# PAGE2.net
KiCad netlist of a schematic drawn in Altium Designer
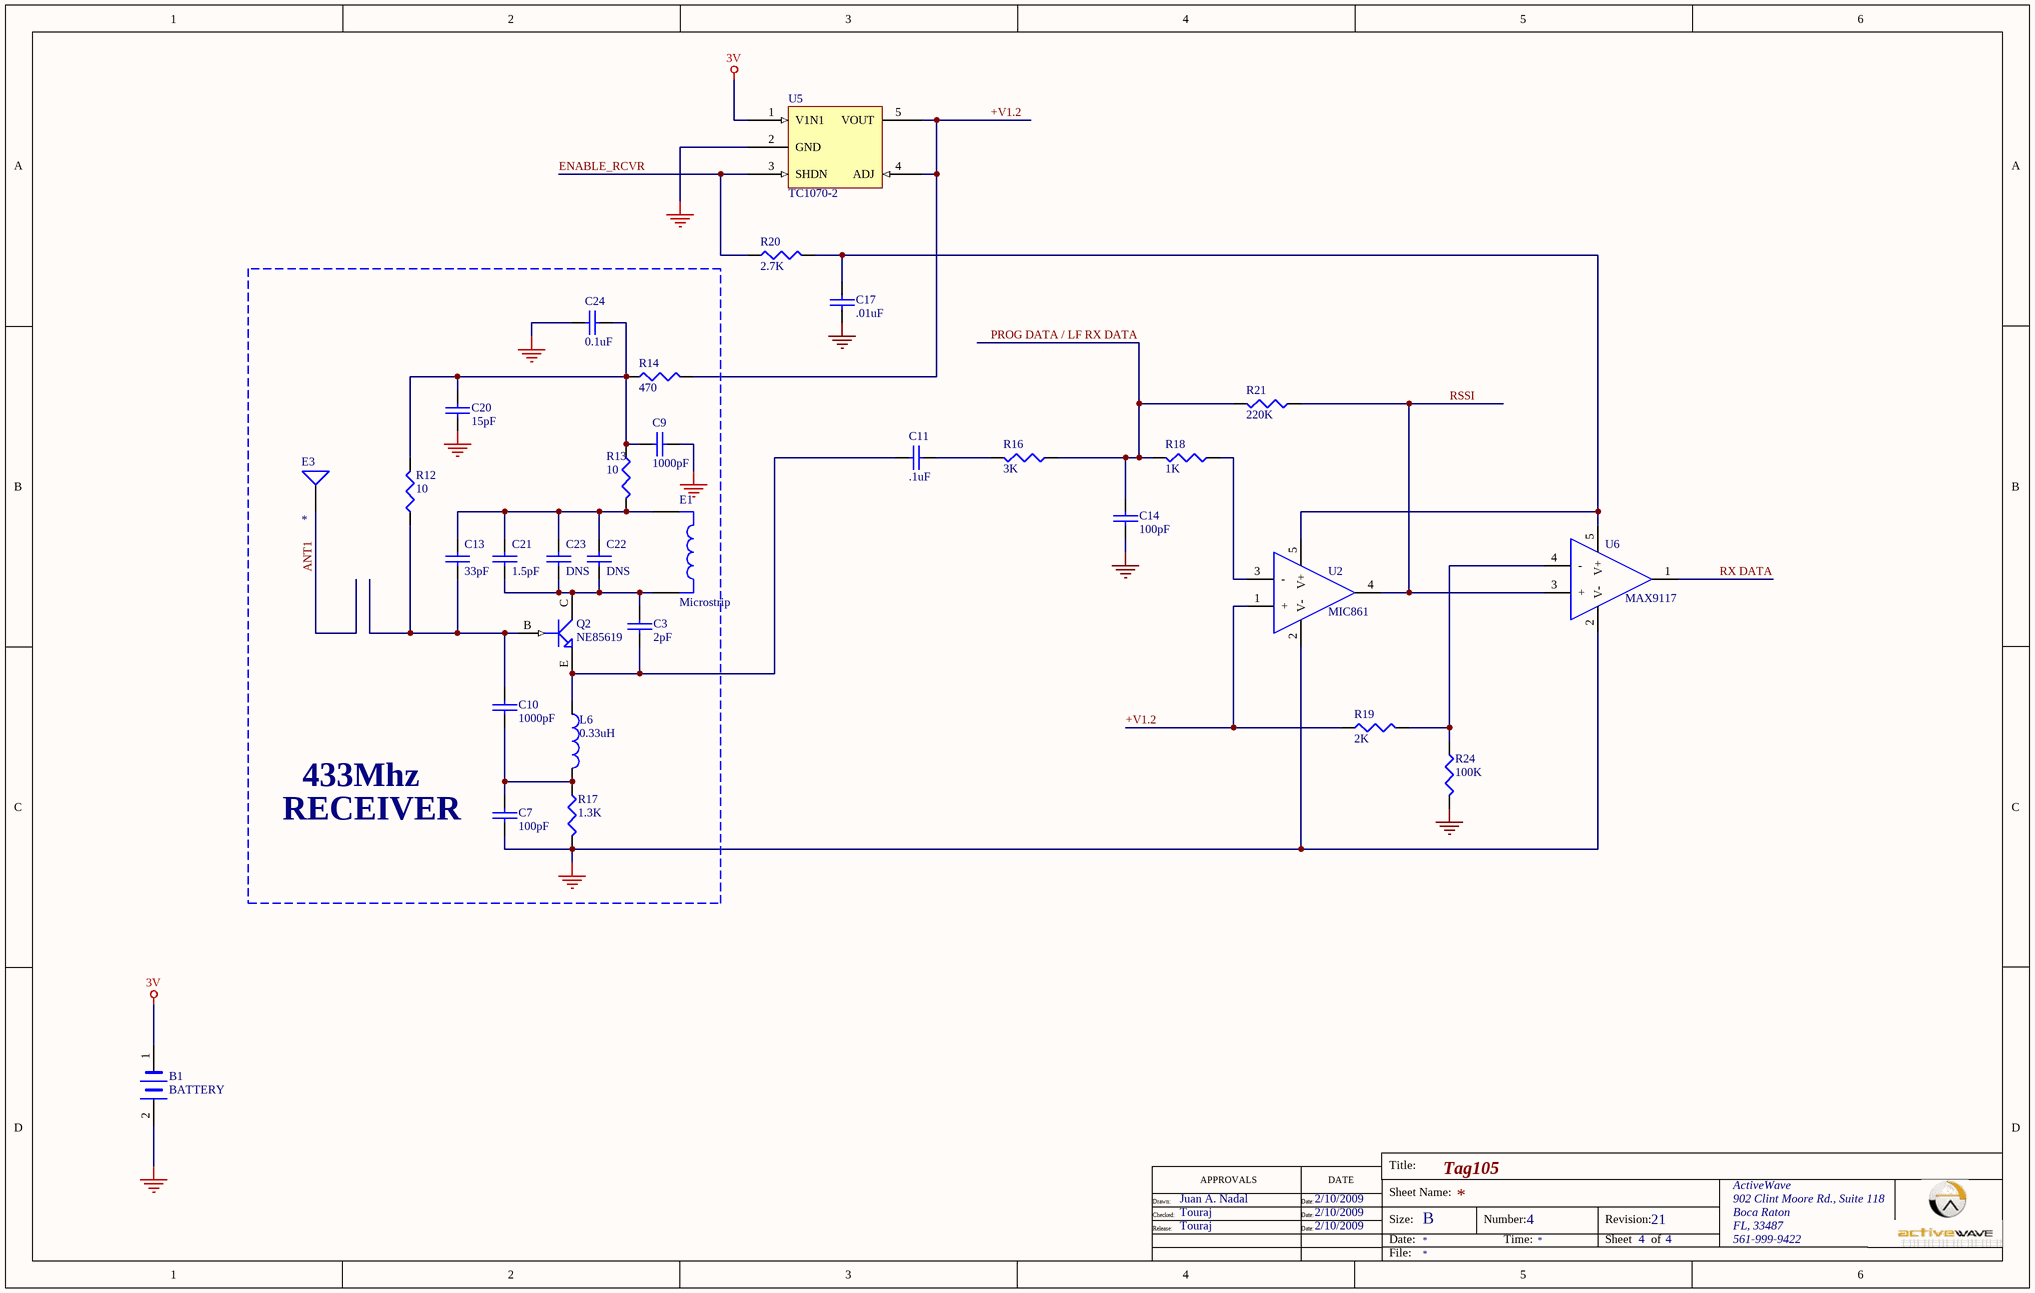
[diagram p0: PAGE2.schdoc]

(export (version "E")
  (design (tool "Eeschema 10.0.6"))
  (components
    (comp (ref "B1")
      (value "BATTERY")
      (footprint "BATTERY COIN CR2032")
      (description "Battery")
      (libsource (lib "*") (part "BATTERY"))
    )
    (comp (ref "C3")
      (value "2pF")
      (footprint "0603")
      (description "Capacitor")
      (libsource (lib "ActiveWave MasterLib") (part "CAP-0603"))
    )
    (comp (ref "C7")
      (value "100pF")
      (footprint "0603")
      (description "Capacitor")
      (libsource (lib "ActiveWave MasterLib") (part "CAP-0603"))
    )
    (comp (ref "C9")
      (value "1000pF")
      (footprint "0603")
      (description "Capacitor")
      (libsource (lib "ActiveWave MasterLib") (part "CAP-0603"))
    )
    (comp (ref "C10")
      (value "1000pF")
      (footprint "0603")
      (description "Capacitor")
      (libsource (lib "ActiveWave MasterLib") (part "CAP-0603"))
    )
    (comp (ref "C11")
      (value ".1uF")
      (footprint "0603")
      (description "Capacitor")
      (libsource (lib "ActiveWave MasterLib") (part "CAP-0603"))
    )
    (comp (ref "C13")
      (value "33pF")
      (footprint "0603")
      (description "Capacitor")
      (libsource (lib "ActiveWave MasterLib") (part "CAP-0603"))
    )
    (comp (ref "C14")
      (value "100pF")
      (footprint "0603")
      (description "Capacitor")
      (libsource (lib "ActiveWave MasterLib") (part "CAP-0603"))
    )
    (comp (ref "C17")
      (value ".01uF")
      (footprint "0603")
      (description "Capacitor")
      (libsource (lib "ActiveWave MasterLib") (part "CAP-0603"))
    )
    (comp (ref "C20")
      (value "15pF")
      (footprint "0603")
      (description "Capacitor")
      (libsource (lib "ActiveWave MasterLib") (part "CAP-0603"))
    )
    (comp (ref "C21")
      (value "1.5pF")
      (footprint "0603")
      (description "Capacitor")
      (libsource (lib "ActiveWave MasterLib") (part "CAP-0603"))
    )
    (comp (ref "C22")
      (value "DNS")
      (footprint "0603")
      (description "Capacitor")
      (libsource (lib "ActiveWave MasterLib") (part "CAP-0603"))
    )
    (comp (ref "C23")
      (value "DNS")
      (footprint "0603")
      (description "Capacitor")
      (libsource (lib "ActiveWave MasterLib") (part "CAP-0603"))
    )
    (comp (ref "C24")
      (value "0.1uF")
      (footprint "0603")
      (description "Capacitor")
      (libsource (lib "ActiveWave MasterLib") (part "CAP-0603"))
    )
    (comp (ref "E1")
      (value "Microstrip")
      (footprint "Antenna")
      (fields (field (name "ITEM-DESCRIPTION") "Microstrip"))
      (libsource (lib "ActiveWave MasterLib") (part "ANTENNA"))
    )
    (comp (ref "E3")
      (value "*")
      (footprint "Antenna1")
      (fields (field (name "ALTIUM_VALUE") "*"))
      (libsource (lib "ActiveWave MasterLib") (part "Antenna1"))
    )
    (comp (ref "L6")
      (value "0.33uH")
      (footprint "0603")
      (libsource (lib "ActiveWave MasterLib") (part "INDUCTOR"))
    )
    (comp (ref "Q2")
      (value "NE85619")
      (footprint "3 PIN ULTRA SUPER MINI MOLD")
      (description "TRANSISTOR NPN 1GHZ SMD")
      (fields (field (name "MANUFACTURER") "??????"))
      (libsource (lib "ActiveWave MasterLib") (part "NE85619"))
    )
    (comp (ref "R12")
      (value "10")
      (footprint "0603")
      (libsource (lib "ActiveWave MasterLib") (part "RES-0603"))
    )
    (comp (ref "R13")
      (value "10")
      (footprint "0603")
      (libsource (lib "ActiveWave MasterLib") (part "RES-0603"))
    )
    (comp (ref "R14")
      (value "470")
      (footprint "0603")
      (libsource (lib "ActiveWave MasterLib") (part "RES-0603"))
    )
    (comp (ref "R16")
      (value "3K")
      (footprint "0603")
      (libsource (lib "ActiveWave MasterLib") (part "RES-0603"))
    )
    (comp (ref "R17")
      (value "1.3K")
      (footprint "0603")
      (libsource (lib "ActiveWave MasterLib") (part "RES-0603"))
    )
    (comp (ref "R18")
      (value "1K")
      (footprint "0603")
      (libsource (lib "ActiveWave MasterLib") (part "RES-0603"))
    )
    (comp (ref "R19")
      (value "2K")
      (footprint "0603")
      (libsource (lib "ActiveWave MasterLib") (part "RES-0603"))
    )
    (comp (ref "R20")
      (value "2.7K")
      (footprint "0603")
      (libsource (lib "ActiveWave MasterLib") (part "RES-0603"))
    )
    (comp (ref "R21")
      (value "220K")
      (footprint "0603")
      (libsource (lib "ActiveWave MasterLib") (part "RES-0603"))
    )
    (comp (ref "R24")
      (value "100K")
      (footprint "0603")
      (libsource (lib "ActiveWave MasterLib") (part "RES-0603"))
    )
    (comp (ref "U2")
      (value "MIC861")
      (footprint "SC70")
      (description "Ultra Low Power Op Amp")
      (fields (field (name "MANUFACTURER") "MICREL"))
      (libsource (lib "ActiveWave MasterLib") (part "MIC861BC5"))
    )
    (comp (ref "U5")
      (value "TC1070-2")
      (footprint "SOT23-5A")
      (description "Adjustable CMOS LDOs with Shutdown")
      (fields (field (name "MANUFACTURER") "Microchip Technology"))
      (libsource (lib "ActiveWave MasterLib") (part "TC1070-2"))
    )
    (comp (ref "U6")
      (value "MAX9117")
      (footprint "SC70")
      (description "MAX9117 Comparators")
      (fields (field (name "MANUFACTURER") "MAXIM"))
      (libsource (lib "ActiveWave MasterLib") (part "COMPARATOR MAX9117"))
    )
  )
  (nets
    (net (code "1") (name "/+V1.2") (class "Default")
      (node (ref "R14") (pin "2") (pinfunction "2_2") (pintype "passive"))
      (node (ref "R19") (pin "1") (pinfunction "1_1") (pintype "passive"))
      (node (ref "U2") (pin "1") (pinfunction "+_1") (pintype "passive"))
      (node (ref "U5") (pin "4") (pinfunction "ADJ_4") (pintype "input"))
      (node (ref "U5") (pin "5") (pinfunction "VOUT_5") (pintype "power_in"))
    )
    (net (code "2") (name "/ANT1") (class "Default")
      (node (ref "E3") (pin "1") (pinfunction "1_1") (pintype "passive"))
    )
    (net (code "3") (name "/ENABLE_RCVR") (class "Default")
      (node (ref "R20") (pin "1") (pinfunction "1_1") (pintype "passive"))
      (node (ref "U5") (pin "3") (pinfunction "SHDN_3") (pintype "input"))
    )
    (net (code "4") (name "/PROG DATA {slash} LF RX DATA") (class "Default")
      (node (ref "C14") (pin "2") (pinfunction "2_2") (pintype "passive"))
      (node (ref "R16") (pin "1") (pinfunction "1_1") (pintype "passive"))
      (node (ref "R18") (pin "2") (pinfunction "2_2") (pintype "passive"))
      (node (ref "R21") (pin "2") (pinfunction "2_2") (pintype "passive"))
    )
    (net (code "5") (name "/RSSI") (class "Default")
      (node (ref "R21") (pin "1") (pinfunction "1_1") (pintype "passive"))
      (node (ref "U2") (pin "4") (pinfunction "OUT_4") (pintype "passive"))
      (node (ref "U6") (pin "3") (pinfunction "+_3") (pintype "passive"))
    )
    (net (code "6") (name "/RX DATA") (class "Default")
      (node (ref "U6") (pin "1") (pinfunction "OUT_1") (pintype "passive"))
    )
    (net (code "7") (name "3V") (class "Default")
      (node (ref "B1") (pin "1") (pinfunction "-_1") (pintype "passive"))
      (node (ref "U5") (pin "1") (pinfunction "V1N1_1") (pintype "input"))
    )
    (net (code "8") (name "GND") (class "Default")
      (node (ref "B1") (pin "2") (pinfunction "+_2") (pintype "passive"))
      (node (ref "C14") (pin "1") (pinfunction "1_1") (pintype "passive"))
      (node (ref "C17") (pin "2") (pinfunction "2_2") (pintype "passive"))
      (node (ref "C20") (pin "2") (pinfunction "2_2") (pintype "passive"))
      (node (ref "C24") (pin "2") (pinfunction "2_2") (pintype "passive"))
      (node (ref "C7") (pin "2") (pinfunction "2_2") (pintype "passive"))
      (node (ref "C9") (pin "2") (pinfunction "2_2") (pintype "passive"))
      (node (ref "R17") (pin "2") (pinfunction "2_2") (pintype "passive"))
      (node (ref "R24") (pin "2") (pinfunction "2_2") (pintype "passive"))
      (node (ref "U2") (pin "2") (pinfunction "V-_2") (pintype "passive"))
      (node (ref "U5") (pin "2") (pinfunction "GND_2") (pintype "power_in"))
      (node (ref "U6") (pin "2") (pinfunction "V-_2") (pintype "passive"))
    )
    (net (code "9") (name "Net-(C10-Pad1)") (class "Default")
      (node (ref "C10") (pin "1") (pinfunction "1_1") (pintype "passive"))
      (node (ref "C13") (pin "2") (pinfunction "2_2") (pintype "passive"))
      (node (ref "Q2") (pin "B") (pinfunction "B_B") (pintype "input"))
      (node (ref "R12") (pin "1") (pinfunction "1_1") (pintype "passive"))
    )
    (net (code "10") (name "Net-(C10-Pad2)") (class "Default")
      (node (ref "C10") (pin "2") (pinfunction "2_2") (pintype "passive"))
      (node (ref "C7") (pin "1") (pinfunction "1_1") (pintype "passive"))
      (node (ref "L6") (pin "2") (pinfunction "2_2") (pintype "passive"))
      (node (ref "R17") (pin "1") (pinfunction "1_1") (pintype "passive"))
    )
    (net (code "11") (name "Net-(C11-Pad1)") (class "Default")
      (node (ref "C11") (pin "1") (pinfunction "1_1") (pintype "passive"))
      (node (ref "C3") (pin "2") (pinfunction "2_2") (pintype "passive"))
      (node (ref "L6") (pin "1") (pinfunction "1_1") (pintype "passive"))
      (node (ref "Q2") (pin "E") (pinfunction "E_E") (pintype "passive"))
    )
    (net (code "12") (name "Net-(C11-Pad2)") (class "Default")
      (node (ref "C11") (pin "2") (pinfunction "2_2") (pintype "passive"))
      (node (ref "R16") (pin "2") (pinfunction "2_2") (pintype "passive"))
    )
    (net (code "13") (name "Net-(C13-Pad1)") (class "Default")
      (node (ref "C13") (pin "1") (pinfunction "1_1") (pintype "passive"))
      (node (ref "C21") (pin "1") (pinfunction "1_1") (pintype "passive"))
      (node (ref "C22") (pin "1") (pinfunction "1_1") (pintype "passive"))
      (node (ref "C23") (pin "1") (pinfunction "1_1") (pintype "passive"))
      (node (ref "E1") (pin "2") (pinfunction "2_2") (pintype "passive"))
      (node (ref "R13") (pin "2") (pinfunction "2_2") (pintype "passive"))
    )
    (net (code "14") (name "Net-(C20-Pad1)") (class "Default")
      (node (ref "C20") (pin "1") (pinfunction "1_1") (pintype "passive"))
      (node (ref "C24") (pin "1") (pinfunction "1_1") (pintype "passive"))
      (node (ref "C9") (pin "1") (pinfunction "1_1") (pintype "passive"))
      (node (ref "R12") (pin "2") (pinfunction "2_2") (pintype "passive"))
      (node (ref "R13") (pin "1") (pinfunction "1_1") (pintype "passive"))
      (node (ref "R14") (pin "1") (pinfunction "1_1") (pintype "passive"))
    )
    (net (code "15") (name "Net-(C21-Pad2)") (class "Default")
      (node (ref "C21") (pin "2") (pinfunction "2_2") (pintype "passive"))
      (node (ref "C22") (pin "2") (pinfunction "2_2") (pintype "passive"))
      (node (ref "C23") (pin "2") (pinfunction "2_2") (pintype "passive"))
      (node (ref "C3") (pin "1") (pinfunction "1_1") (pintype "passive"))
      (node (ref "E1") (pin "1") (pinfunction "1_1") (pintype "passive"))
      (node (ref "Q2") (pin "C") (pinfunction "C_C") (pintype "passive"))
    )
    (net (code "16") (name "Net-(U2--)") (class "Default")
      (node (ref "R18") (pin "1") (pinfunction "1_1") (pintype "passive"))
      (node (ref "U2") (pin "3") (pinfunction "-_3") (pintype "passive"))
    )
    (net (code "17") (name "Net-(U2-V+)") (class "Default")
      (node (ref "C17") (pin "1") (pinfunction "1_1") (pintype "passive"))
      (node (ref "R20") (pin "2") (pinfunction "2_2") (pintype "passive"))
      (node (ref "U2") (pin "5") (pinfunction "V+_5") (pintype "passive"))
      (node (ref "U6") (pin "5") (pinfunction "V+_5") (pintype "passive"))
    )
    (net (code "18") (name "Net-(U6--)") (class "Default")
      (node (ref "R19") (pin "2") (pinfunction "2_2") (pintype "passive"))
      (node (ref "R24") (pin "1") (pinfunction "1_1") (pintype "passive"))
      (node (ref "U6") (pin "4") (pinfunction "-_4") (pintype "passive"))
    )
  )
)
